# Nu_Duo.net
KiCad netlist of a schematic drawn in EAGLE
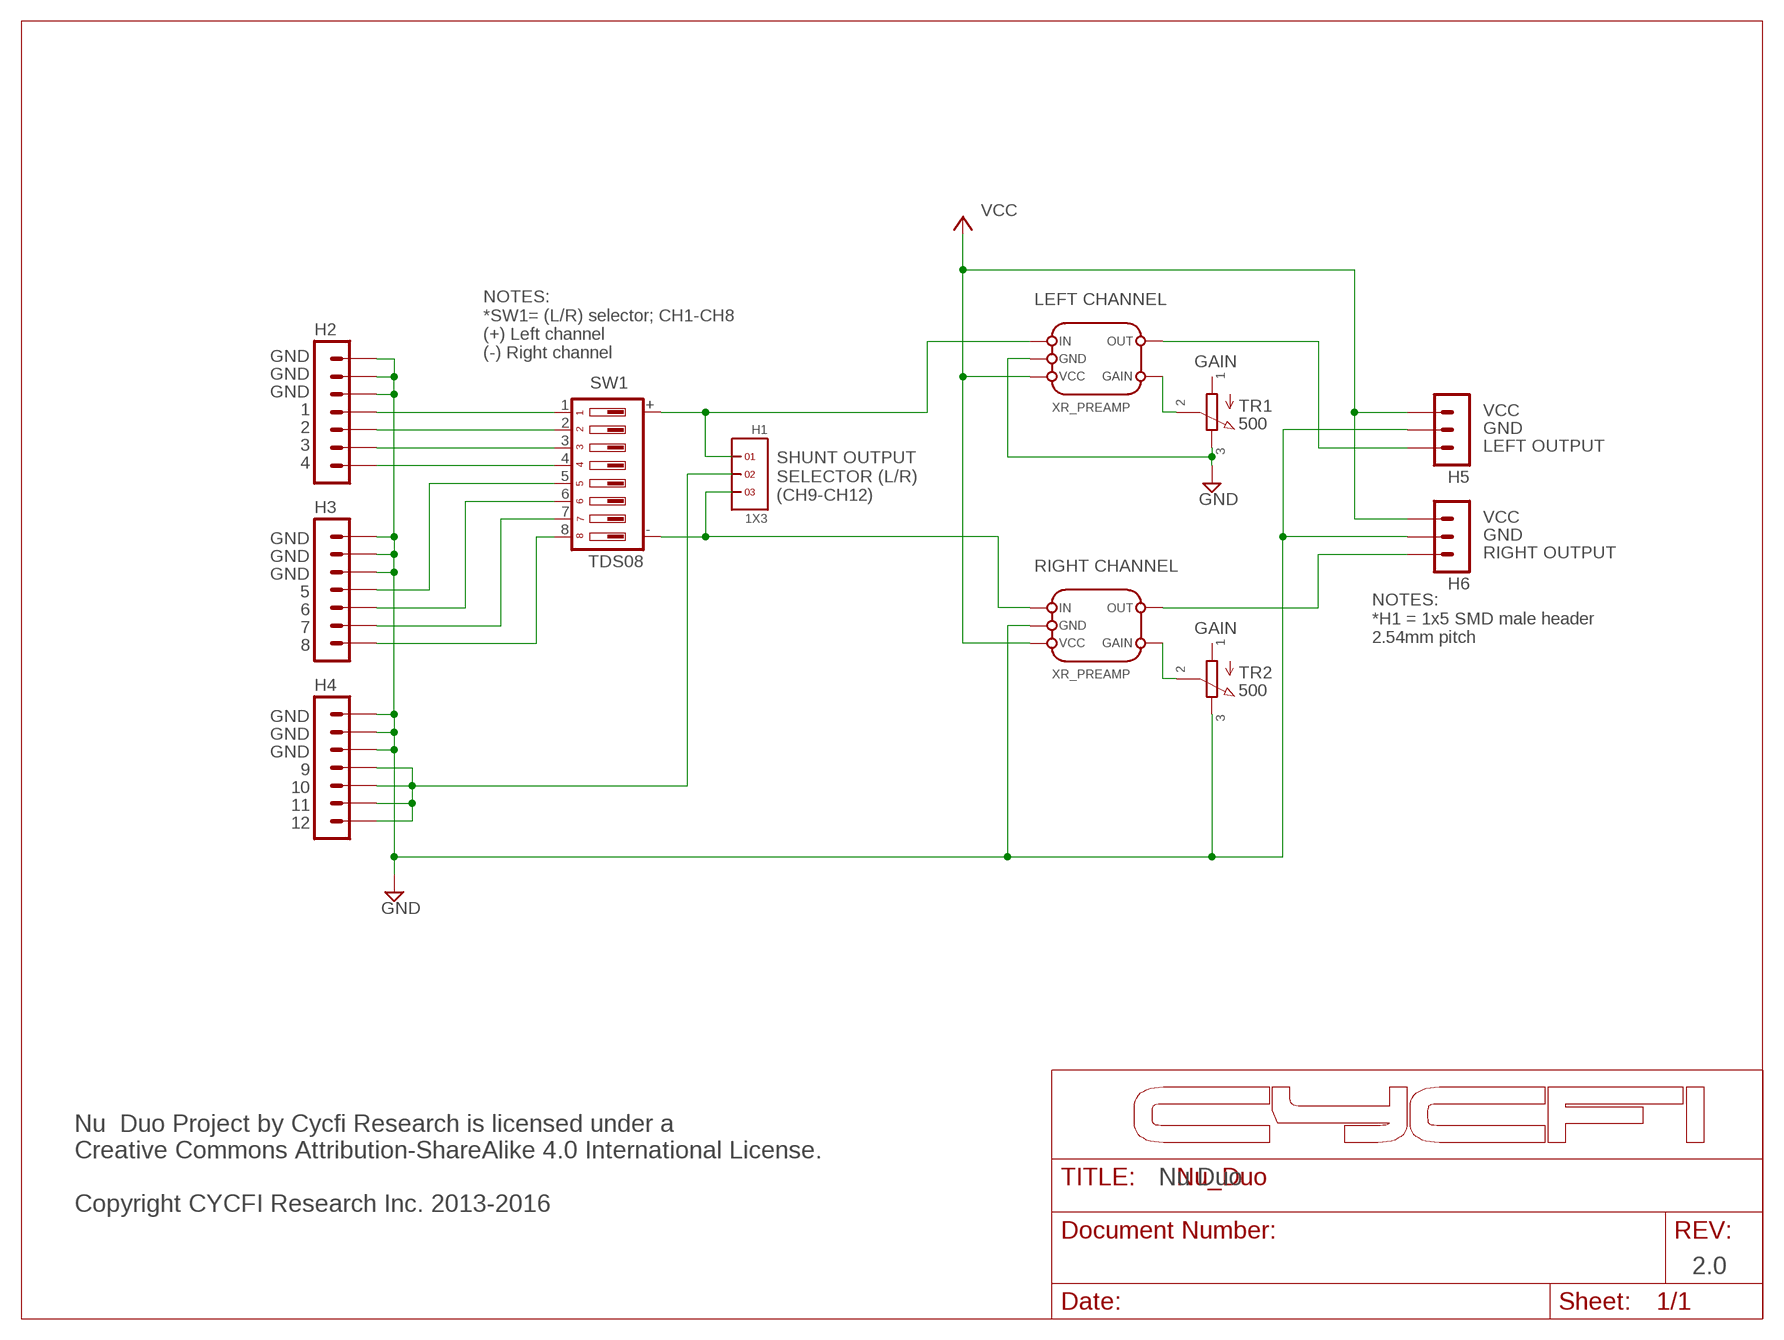
[diagram p0: schematic, sheet 1]

(export (version "E")
  (design (tool "Eeschema 10.0.6"))
  (components
    (comp (ref "H1")
      (value "1X3")
      (footprint "eagle-import:1X3")
      (libsource (lib "eagle-import") (part "1X3"))
    )
    (comp (ref "H2")
      (value "7P_ZIF_59453-071110EDHLF")
      (footprint "eagle-import:7P_ZIF_59453-071110EDHLF")
      (libsource (lib "eagle-import") (part "7P_ZIF_59453-071110EDHLF"))
    )
    (comp (ref "H3")
      (value "7P_ZIF_59453-071110EDHLF")
      (footprint "eagle-import:7P_ZIF_59453-071110EDHLF")
      (libsource (lib "eagle-import") (part "7P_ZIF_59453-071110EDHLF"))
    )
    (comp (ref "H4")
      (value "7P_ZIF_59453-071110EDHLF")
      (footprint "eagle-import:7P_ZIF_59453-071110EDHLF")
      (libsource (lib "eagle-import") (part "7P_ZIF_59453-071110EDHLF"))
    )
    (comp (ref "H5")
      (value "3PIN-SMD-2.54MM")
      (footprint "eagle-import:3P-SMD-2.54MM")
      (libsource (lib "eagle-import") (part "3PIN-SMD-2.54MM"))
    )
    (comp (ref "H6")
      (value "3PIN-SMD-2.54MM")
      (footprint "eagle-import:3P-SMD-2.54MM")
      (libsource (lib "eagle-import") (part "3PIN-SMD-2.54MM"))
    )
    (comp (ref "P1")
      (value "XR_PREAMP")
      (footprint "eagle-import:XR_PREAMP_V1.5")
      (libsource (lib "eagle-import") (part "XR_PREAMP"))
    )
    (comp (ref "P2")
      (value "XR_PREAMP")
      (footprint "eagle-import:XR_PREAMP_V1.5")
      (libsource (lib "eagle-import") (part "XR_PREAMP"))
    )
    (comp (ref "SW1")
      (value "TDS08")
      (footprint "eagle-import:SPDT-08")
      (libsource (lib "eagle-import") (part "TDS08"))
    )
    (comp (ref "TR1")
      (value "500")
      (footprint "eagle-import:TC33X-2-201E")
      (libsource (lib "eagle-import") (part "TC33X-2-201E"))
    )
    (comp (ref "TR2")
      (value "500")
      (footprint "eagle-import:TC33X-2-201E")
      (libsource (lib "eagle-import") (part "TC33X-2-201E"))
    )
  )
  (nets
    (net (code "1") (name "GND") (class "Default")
      (node (ref "H2") (pin "P$5") (pinfunction "5_P$5") (pintype "passive"))
      (node (ref "H2") (pin "P$6") (pinfunction "6_P$6") (pintype "passive"))
      (node (ref "H2") (pin "P$7") (pinfunction "7_P$7") (pintype "passive"))
      (node (ref "H3") (pin "P$5") (pinfunction "5_P$5") (pintype "passive"))
      (node (ref "H3") (pin "P$6") (pinfunction "6_P$6") (pintype "passive"))
      (node (ref "H3") (pin "P$7") (pinfunction "7_P$7") (pintype "passive"))
      (node (ref "H4") (pin "P$5") (pinfunction "5_P$5") (pintype "passive"))
      (node (ref "H4") (pin "P$6") (pinfunction "6_P$6") (pintype "passive"))
      (node (ref "H4") (pin "P$7") (pinfunction "7_P$7") (pintype "passive"))
      (node (ref "H5") (pin "P$2") (pinfunction "2_P$2") (pintype "passive"))
      (node (ref "H6") (pin "P$2") (pinfunction "2_P$2") (pintype "passive"))
      (node (ref "P1") (pin "GND") (pinfunction "GND_GND") (pintype "bidirectional"))
      (node (ref "P2") (pin "GND") (pinfunction "GND_GND") (pintype "bidirectional"))
      (node (ref "TR1") (pin "P$3") (pinfunction "3_P$3") (pintype "passive"))
      (node (ref "TR2") (pin "P$3") (pinfunction "3_P$3") (pintype "passive"))
    )
    (net (code "2") (name "Net-(H1-Pad1)") (class "Default")
      (node (ref "H1") (pin "1") (pinfunction "1_1") (pintype "bidirectional"))
      (node (ref "P1") (pin "IN") (pinfunction "IN_IN") (pintype "bidirectional"))
      (node (ref "SW1") (pin "+") (pinfunction "+_+") (pintype "passive"))
    )
    (net (code "3") (name "Net-(H1-Pad3)") (class "Default")
      (node (ref "H1") (pin "3") (pinfunction "3_3") (pintype "bidirectional"))
      (node (ref "P2") (pin "IN") (pinfunction "IN_IN") (pintype "bidirectional"))
      (node (ref "SW1") (pin "-") (pinfunction "-_-") (pintype "passive"))
    )
    (net (code "4") (name "Net-(H2-1)") (class "Default")
      (node (ref "H2") (pin "P$1") (pinfunction "1_P$1") (pintype "passive"))
      (node (ref "SW1") (pin "4") (pinfunction "4_4") (pintype "passive"))
    )
    (net (code "5") (name "Net-(H2-2)") (class "Default")
      (node (ref "H2") (pin "P$2") (pinfunction "2_P$2") (pintype "passive"))
      (node (ref "SW1") (pin "3") (pinfunction "3_3") (pintype "passive"))
    )
    (net (code "6") (name "Net-(H2-3)") (class "Default")
      (node (ref "H2") (pin "P$3") (pinfunction "3_P$3") (pintype "passive"))
      (node (ref "SW1") (pin "2") (pinfunction "2_2") (pintype "passive"))
    )
    (net (code "7") (name "Net-(H2-4)") (class "Default")
      (node (ref "H2") (pin "P$4") (pinfunction "4_P$4") (pintype "passive"))
      (node (ref "SW1") (pin "1") (pinfunction "1_1") (pintype "passive"))
    )
    (net (code "8") (name "Net-(H3-1)") (class "Default")
      (node (ref "H3") (pin "P$1") (pinfunction "1_P$1") (pintype "passive"))
      (node (ref "SW1") (pin "8") (pinfunction "8_8") (pintype "passive"))
    )
    (net (code "9") (name "Net-(H3-2)") (class "Default")
      (node (ref "H3") (pin "P$2") (pinfunction "2_P$2") (pintype "passive"))
      (node (ref "SW1") (pin "7") (pinfunction "7_7") (pintype "passive"))
    )
    (net (code "10") (name "Net-(H3-3)") (class "Default")
      (node (ref "H3") (pin "P$3") (pinfunction "3_P$3") (pintype "passive"))
      (node (ref "SW1") (pin "6") (pinfunction "6_6") (pintype "passive"))
    )
    (net (code "11") (name "Net-(H3-4)") (class "Default")
      (node (ref "H3") (pin "P$4") (pinfunction "4_P$4") (pintype "passive"))
      (node (ref "SW1") (pin "5") (pinfunction "5_5") (pintype "passive"))
    )
    (net (code "12") (name "Net-(H4-1)") (class "Default")
      (node (ref "H1") (pin "2") (pinfunction "2_2") (pintype "bidirectional"))
      (node (ref "H4") (pin "P$1") (pinfunction "1_P$1") (pintype "passive"))
      (node (ref "H4") (pin "P$2") (pinfunction "2_P$2") (pintype "passive"))
      (node (ref "H4") (pin "P$3") (pinfunction "3_P$3") (pintype "passive"))
      (node (ref "H4") (pin "P$4") (pinfunction "4_P$4") (pintype "passive"))
    )
    (net (code "13") (name "Net-(H5-3)") (class "Default")
      (node (ref "H5") (pin "P$3") (pinfunction "3_P$3") (pintype "passive"))
      (node (ref "P1") (pin "OUT") (pinfunction "OUT_OUT") (pintype "bidirectional"))
    )
    (net (code "14") (name "Net-(H6-3)") (class "Default")
      (node (ref "H6") (pin "P$3") (pinfunction "3_P$3") (pintype "passive"))
      (node (ref "P2") (pin "OUT") (pinfunction "OUT_OUT") (pintype "bidirectional"))
    )
    (net (code "15") (name "Net-(TR1-2)") (class "Default")
      (node (ref "P1") (pin "GAIN") (pinfunction "GAIN_GAIN") (pintype "bidirectional"))
      (node (ref "TR1") (pin "P$2") (pinfunction "2_P$2") (pintype "passive"))
    )
    (net (code "16") (name "Net-(TR2-2)") (class "Default")
      (node (ref "P2") (pin "GAIN") (pinfunction "GAIN_GAIN") (pintype "bidirectional"))
      (node (ref "TR2") (pin "P$2") (pinfunction "2_P$2") (pintype "passive"))
    )
    (net (code "17") (name "VCC") (class "Default")
      (node (ref "H5") (pin "P$1") (pinfunction "1_P$1") (pintype "passive"))
      (node (ref "H6") (pin "P$1") (pinfunction "1_P$1") (pintype "passive"))
      (node (ref "P1") (pin "VCC") (pinfunction "VCC_VCC") (pintype "bidirectional"))
      (node (ref "P2") (pin "VCC") (pinfunction "VCC_VCC") (pintype "bidirectional"))
    )
    (net (code "18") (name "unconnected-(TR1-1-PadP$1)") (class "Default")
      (node (ref "TR1") (pin "P$1") (pinfunction "1_P$1") (pintype "passive"))
    )
    (net (code "19") (name "unconnected-(TR2-1-PadP$1)") (class "Default")
      (node (ref "TR2") (pin "P$1") (pinfunction "1_P$1") (pintype "passive"))
    )
  )
)
